# Main.net
KiCad netlist of a schematic drawn in Altium Designer
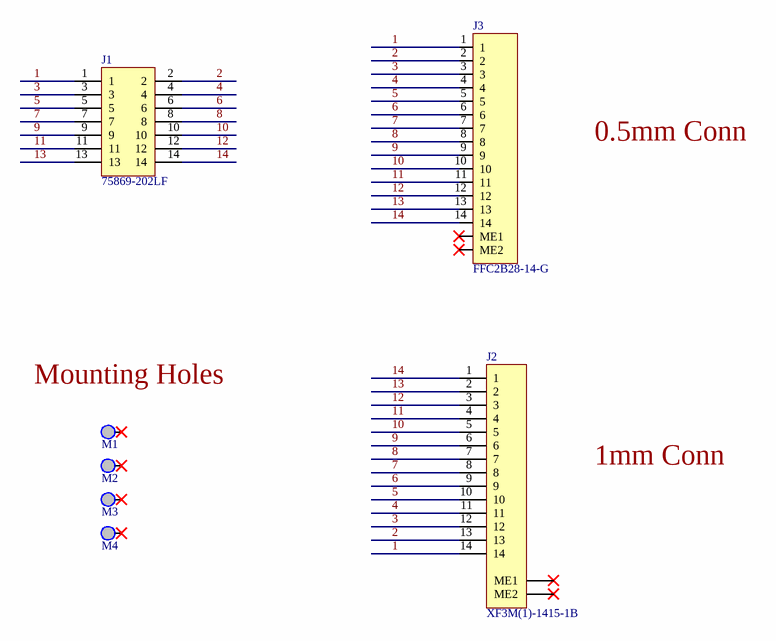
[diagram p0: Main.SchDoc]

(export (version "E")
  (design (tool "Eeschema 10.0.6"))
  (components
    (comp (ref "J1")
      (value "75869-202LF")
      (footprint "HDR-V-2x7-KEYED")
      (description "Headers & Wire Housings 14P DR VERT SHRD HDR TIN")
      (libsource (lib "intercreate") (part "HDR-V-2x7-M"))
    )
    (comp (ref "J2")
      (value "XF3M(1)-1415-1B")
      (footprint "CONN-FFC-H-14P-1MM")
      (description "1.0-mm Pitch, Dual Contact ; For FPC/FFC, 14 Contacts, RoHS")
      (libsource (lib "intercreate") (part "CONN-FFC-H-14P-1MM"))
    )
    (comp (ref "J3")
      (value "FFC2B28-14-G")
      (footprint "CONN-FFC-H-14P-0.5MM")
      (description "14W, 0.5MM Ffc Con, R/a, Dual Cont,")
      (libsource (lib "intercreate") (part "CONN-FFC-H-14P-0.5MM"))
    )
    (comp (ref "M1")
      (value "MTG_HOLE")
      (footprint "MH_P_2.5MM")
      (description "MTG HOLE PLATED VARIOUS SIZES")
      (libsource (lib "intercreate") (part "MTG_HOLE"))
    )
    (comp (ref "M2")
      (value "MTG_HOLE")
      (footprint "MH_P_2.5MM")
      (description "MTG HOLE PLATED VARIOUS SIZES")
      (libsource (lib "intercreate") (part "MTG_HOLE"))
    )
    (comp (ref "M3")
      (value "MTG_HOLE")
      (footprint "MH_P_2.5MM")
      (description "MTG HOLE PLATED VARIOUS SIZES")
      (libsource (lib "intercreate") (part "MTG_HOLE"))
    )
    (comp (ref "M4")
      (value "MTG_HOLE")
      (footprint "MH_P_2.5MM")
      (description "MTG HOLE PLATED VARIOUS SIZES")
      (libsource (lib "intercreate") (part "MTG_HOLE"))
    )
  )
  (nets
    (net (code "1") (name "/1") (class "Default")
      (node (ref "J1") (pin "1") (pinfunction "1_1") (pintype "passive"))
      (node (ref "J2") (pin "14") (pinfunction "14_14") (pintype "passive"))
      (node (ref "J3") (pin "1") (pinfunction "1_1") (pintype "passive"))
    )
    (net (code "2") (name "/2") (class "Default")
      (node (ref "J1") (pin "2") (pinfunction "2_2") (pintype "passive"))
      (node (ref "J2") (pin "13") (pinfunction "13_13") (pintype "passive"))
      (node (ref "J3") (pin "2") (pinfunction "2_2") (pintype "passive"))
    )
    (net (code "3") (name "/3") (class "Default")
      (node (ref "J1") (pin "3") (pinfunction "3_3") (pintype "passive"))
      (node (ref "J2") (pin "12") (pinfunction "12_12") (pintype "passive"))
      (node (ref "J3") (pin "3") (pinfunction "3_3") (pintype "passive"))
    )
    (net (code "4") (name "/4") (class "Default")
      (node (ref "J1") (pin "4") (pinfunction "4_4") (pintype "passive"))
      (node (ref "J2") (pin "11") (pinfunction "11_11") (pintype "passive"))
      (node (ref "J3") (pin "4") (pinfunction "4_4") (pintype "passive"))
    )
    (net (code "5") (name "/5") (class "Default")
      (node (ref "J1") (pin "5") (pinfunction "5_5") (pintype "passive"))
      (node (ref "J2") (pin "10") (pinfunction "10_10") (pintype "passive"))
      (node (ref "J3") (pin "5") (pinfunction "5_5") (pintype "passive"))
    )
    (net (code "6") (name "/6") (class "Default")
      (node (ref "J1") (pin "6") (pinfunction "6_6") (pintype "passive"))
      (node (ref "J2") (pin "9") (pinfunction "9_9") (pintype "passive"))
      (node (ref "J3") (pin "6") (pinfunction "6_6") (pintype "passive"))
    )
    (net (code "7") (name "/7") (class "Default")
      (node (ref "J1") (pin "7") (pinfunction "7_7") (pintype "passive"))
      (node (ref "J2") (pin "8") (pinfunction "8_8") (pintype "passive"))
      (node (ref "J3") (pin "7") (pinfunction "7_7") (pintype "passive"))
    )
    (net (code "8") (name "/8") (class "Default")
      (node (ref "J1") (pin "8") (pinfunction "8_8") (pintype "passive"))
      (node (ref "J2") (pin "7") (pinfunction "7_7") (pintype "passive"))
      (node (ref "J3") (pin "8") (pinfunction "8_8") (pintype "passive"))
    )
    (net (code "9") (name "/9") (class "Default")
      (node (ref "J1") (pin "9") (pinfunction "9_9") (pintype "passive"))
      (node (ref "J2") (pin "6") (pinfunction "6_6") (pintype "passive"))
      (node (ref "J3") (pin "9") (pinfunction "9_9") (pintype "passive"))
    )
    (net (code "10") (name "/10") (class "Default")
      (node (ref "J1") (pin "10") (pinfunction "10_10") (pintype "passive"))
      (node (ref "J2") (pin "5") (pinfunction "5_5") (pintype "passive"))
      (node (ref "J3") (pin "10") (pinfunction "10_10") (pintype "passive"))
    )
    (net (code "11") (name "/11") (class "Default")
      (node (ref "J1") (pin "11") (pinfunction "11_11") (pintype "power_in"))
      (node (ref "J2") (pin "4") (pinfunction "4_4") (pintype "passive"))
      (node (ref "J3") (pin "11") (pinfunction "11_11") (pintype "passive"))
    )
    (net (code "12") (name "/12") (class "Default")
      (node (ref "J1") (pin "12") (pinfunction "12_12") (pintype "power_in"))
      (node (ref "J2") (pin "3") (pinfunction "3_3") (pintype "passive"))
      (node (ref "J3") (pin "12") (pinfunction "12_12") (pintype "passive"))
    )
    (net (code "13") (name "/13") (class "Default")
      (node (ref "J1") (pin "13") (pinfunction "13_13") (pintype "power_in"))
      (node (ref "J2") (pin "2") (pinfunction "2_2") (pintype "passive"))
      (node (ref "J3") (pin "13") (pinfunction "13_13") (pintype "passive"))
    )
    (net (code "14") (name "/14") (class "Default")
      (node (ref "J1") (pin "14") (pinfunction "14_14") (pintype "power_in"))
      (node (ref "J2") (pin "1") (pinfunction "1_1") (pintype "passive"))
      (node (ref "J3") (pin "14") (pinfunction "14_14") (pintype "passive"))
    )
    (net (code "15") (name "unconnected-(J2-PadME1)") (class "Default")
      (node (ref "J2") (pin "ME1") (pinfunction "ME1_ME1") (pintype "passive+no_connect"))
    )
    (net (code "16") (name "unconnected-(J2-PadME2)") (class "Default")
      (node (ref "J2") (pin "ME2") (pinfunction "ME2_ME2") (pintype "passive+no_connect"))
    )
    (net (code "17") (name "unconnected-(J3-PadME1)") (class "Default")
      (node (ref "J3") (pin "ME1") (pinfunction "ME1_ME1") (pintype "passive+no_connect"))
    )
    (net (code "18") (name "unconnected-(J3-PadME2)") (class "Default")
      (node (ref "J3") (pin "ME2") (pinfunction "ME2_ME2") (pintype "passive+no_connect"))
    )
    (net (code "19") (name "unconnected-(M1-Pad1)") (class "Default")
      (node (ref "M1") (pin "1") (pinfunction "1_1") (pintype "passive+no_connect"))
    )
    (net (code "20") (name "unconnected-(M2-Pad1)") (class "Default")
      (node (ref "M2") (pin "1") (pinfunction "1_1") (pintype "passive+no_connect"))
    )
    (net (code "21") (name "unconnected-(M3-Pad1)") (class "Default")
      (node (ref "M3") (pin "1") (pinfunction "1_1") (pintype "passive+no_connect"))
    )
    (net (code "22") (name "unconnected-(M4-Pad1)") (class "Default")
      (node (ref "M4") (pin "1") (pinfunction "1_1") (pintype "passive+no_connect"))
    )
  )
)
